# Module_Expansion_Mosfet.net
KiCad netlist of a schematic drawn in EAGLE
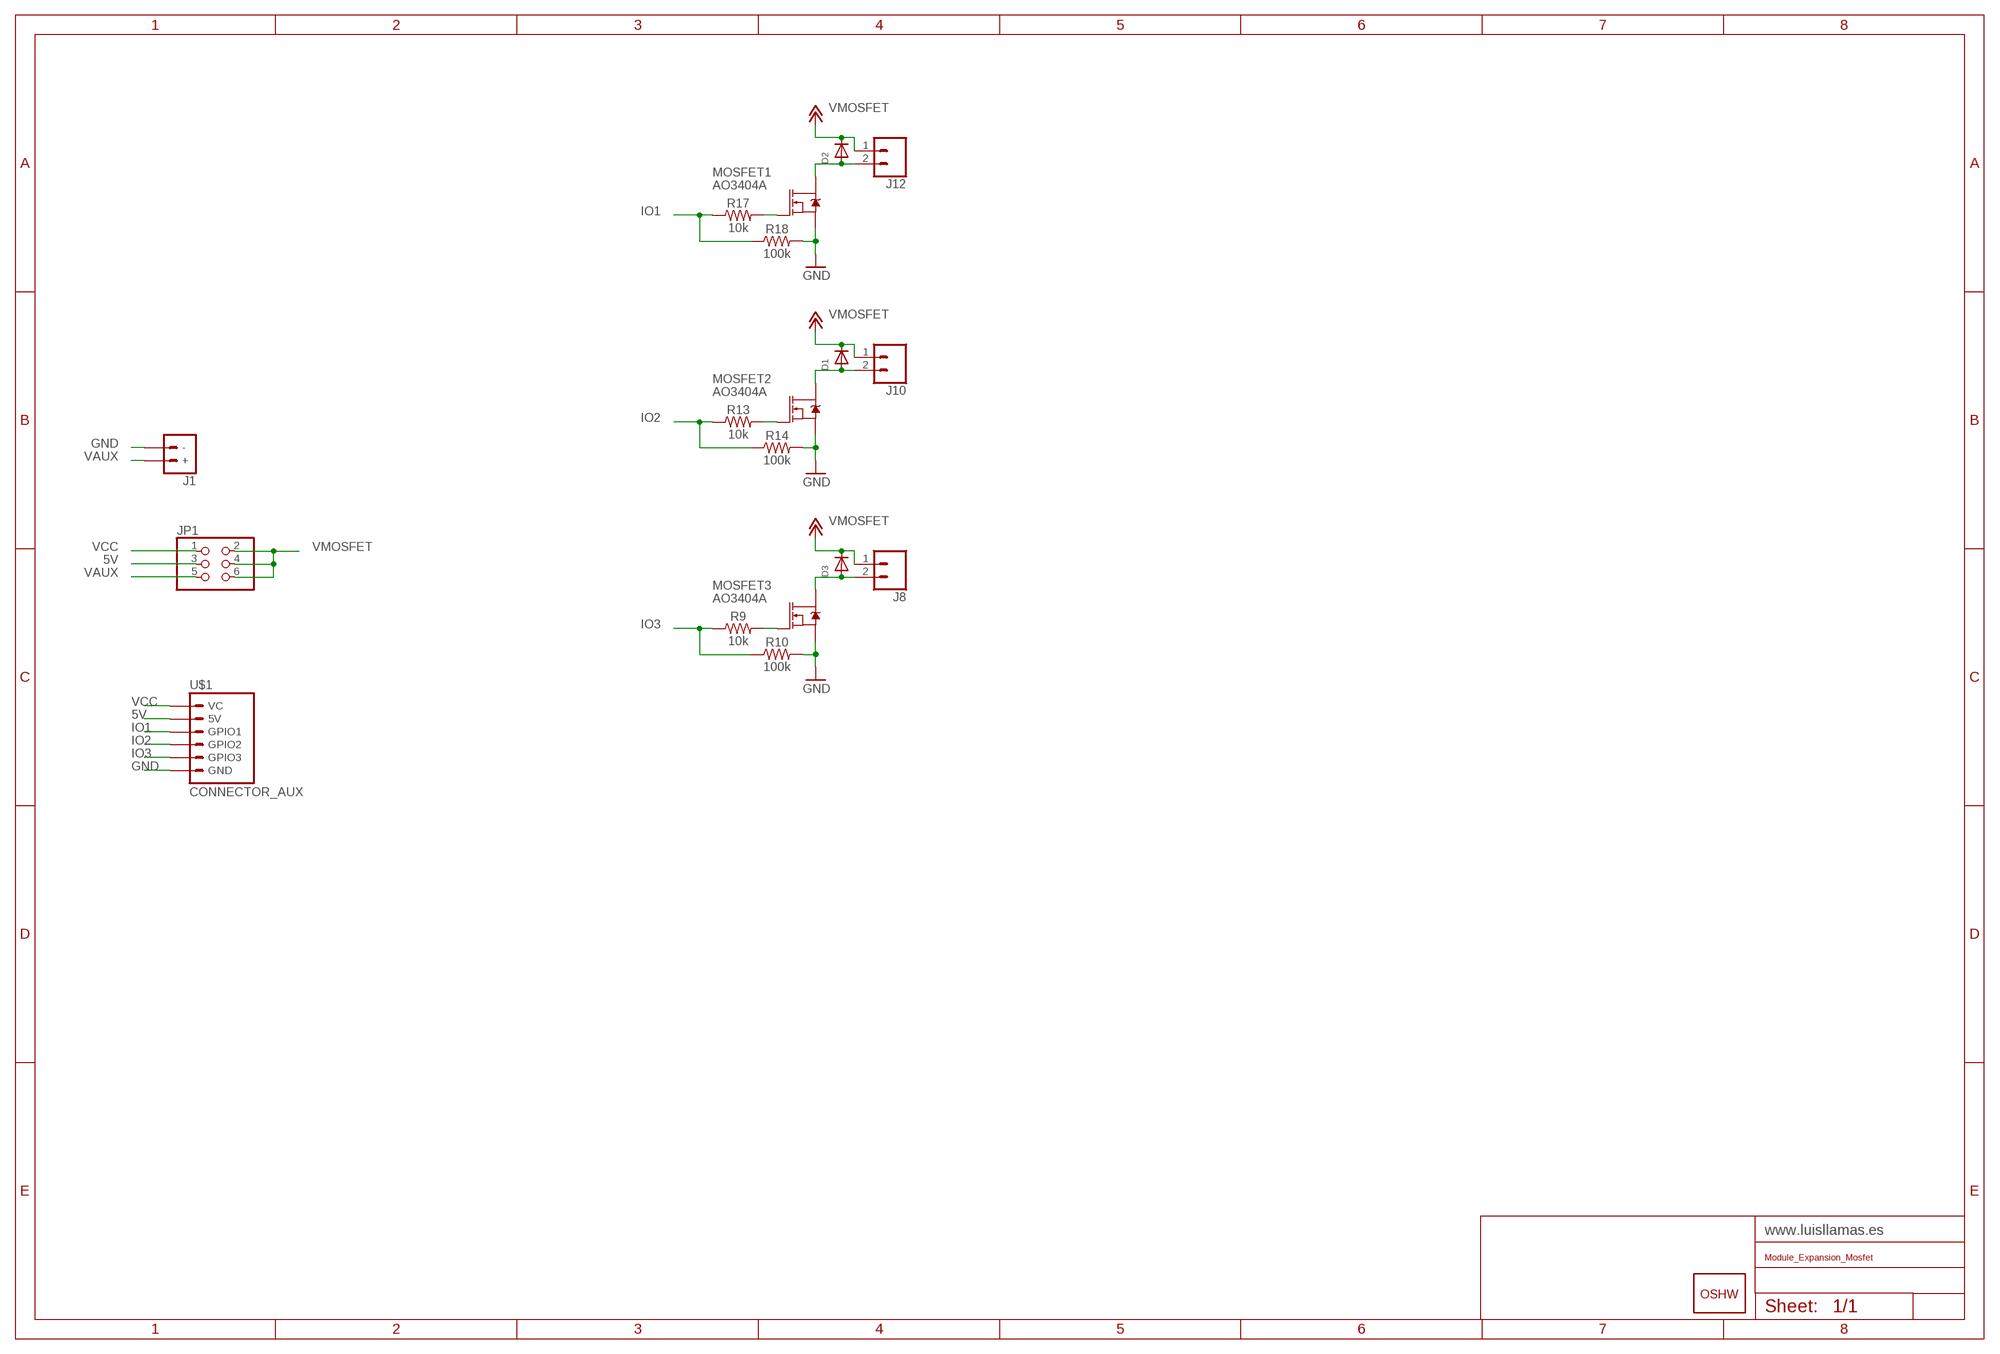
[diagram p0: schematic, sheet 1]

(export (version "E")
  (design (tool "Eeschema 10.0.6"))
  (components
    (comp (ref "D1")
      (value "DIODESOD-123")
      (footprint "eagle-import:SOD-123")
      (libsource (lib "eagle-import") (part "DIODESOD-123"))
    )
    (comp (ref "D2")
      (value "DIODESOD-123")
      (footprint "eagle-import:SOD-123")
      (libsource (lib "eagle-import") (part "DIODESOD-123"))
    )
    (comp (ref "D3")
      (value "DIODESOD-123")
      (footprint "eagle-import:SOD-123")
      (libsource (lib "eagle-import") (part "DIODESOD-123"))
    )
    (comp (ref "GOLD_ORB_SM1")
      (value "OSHWLOGO_GOLD_ORB_MED")
      (footprint "eagle-import:OSHW1")
      (libsource (lib "eagle-import") (part "OSHWLOGO_GOLD_ORB_MED"))
    )
    (comp (ref "J1")
      (value "POWER-TERMINAL2.54MM_SCREWTERM")
      (footprint "eagle-import:1X02_2.54_SCREWTERM")
      (libsource (lib "eagle-import") (part "POWER-TERMINAL2.54MM_SCREWTERM"))
    )
    (comp (ref "J8")
      (value "CONN_02LOCK_LONGPADS")
      (footprint "eagle-import:1X02_LOCK_LONGPADS")
      (libsource (lib "eagle-import") (part "CONN_02LOCK_LONGPADS"))
    )
    (comp (ref "J10")
      (value "CONN_02LOCK_LONGPADS")
      (footprint "eagle-import:1X02_LOCK_LONGPADS")
      (libsource (lib "eagle-import") (part "CONN_02LOCK_LONGPADS"))
    )
    (comp (ref "J12")
      (value "CONN_02LOCK_LONGPADS")
      (footprint "eagle-import:1X02_LOCK_LONGPADS")
      (libsource (lib "eagle-import") (part "CONN_02LOCK_LONGPADS"))
    )
    (comp (ref "JP1")
      (value "JUMPER_3X2/OCT")
      (footprint "eagle-import:JUMPER_3X2")
      (libsource (lib "eagle-import") (part "JUMPER_3X2/OCT"))
    )
    (comp (ref "MOSFET1")
      (value "AO3404A")
      (footprint "eagle-import:SOT23-3")
      (libsource (lib "eagle-import") (part "MOSFET-NCH-AO3404A"))
    )
    (comp (ref "MOSFET2")
      (value "AO3404A")
      (footprint "eagle-import:SOT23-3")
      (libsource (lib "eagle-import") (part "MOSFET-NCH-AO3404A"))
    )
    (comp (ref "MOSFET3")
      (value "AO3404A")
      (footprint "eagle-import:SOT23-3")
      (libsource (lib "eagle-import") (part "MOSFET-NCH-AO3404A"))
    )
    (comp (ref "R9")
      (value "10k")
      (footprint "eagle-import:1206")
      (libsource (lib "eagle-import") (part "RESISTOR1206"))
    )
    (comp (ref "R10")
      (value "100k")
      (footprint "eagle-import:1206")
      (libsource (lib "eagle-import") (part "RESISTOR1206"))
    )
    (comp (ref "R13")
      (value "10k")
      (footprint "eagle-import:1206")
      (libsource (lib "eagle-import") (part "RESISTOR1206"))
    )
    (comp (ref "R14")
      (value "100k")
      (footprint "eagle-import:1206")
      (libsource (lib "eagle-import") (part "RESISTOR1206"))
    )
    (comp (ref "R17")
      (value "10k")
      (footprint "eagle-import:1206")
      (libsource (lib "eagle-import") (part "RESISTOR1206"))
    )
    (comp (ref "R18")
      (value "100k")
      (footprint "eagle-import:1206")
      (libsource (lib "eagle-import") (part "RESISTOR1206"))
    )
    (comp (ref "U$1")
      (value "CONNECTOR_AUX")
      (footprint "eagle-import:CONNECTOR_AUX")
      (libsource (lib "eagle-import") (part "CONNECTOR_AUX"))
    )
  )
  (nets
    (net (code "1") (name "+12V") (class "Default")
      (node (ref "D1") (pin "C") (pinfunction "C_C") (pintype "passive"))
      (node (ref "D2") (pin "C") (pinfunction "C_C") (pintype "passive"))
      (node (ref "D3") (pin "C") (pinfunction "C_C") (pintype "passive"))
      (node (ref "J10") (pin "1") (pinfunction "1_1") (pintype "passive"))
      (node (ref "J12") (pin "1") (pinfunction "1_1") (pintype "passive"))
      (node (ref "J8") (pin "1") (pinfunction "1_1") (pintype "passive"))
      (node (ref "JP1") (pin "2") (pinfunction "2_2") (pintype "passive"))
      (node (ref "JP1") (pin "4") (pinfunction "4_4") (pintype "passive"))
      (node (ref "JP1") (pin "6") (pinfunction "6_6") (pintype "passive"))
    )
    (net (code "2") (name "/5V") (class "Default")
      (node (ref "JP1") (pin "3") (pinfunction "3_3") (pintype "passive"))
      (node (ref "U$1") (pin "5V") (pinfunction "5V_5V") (pintype "passive"))
    )
    (net (code "3") (name "/IO1") (class "Default")
      (node (ref "R17") (pin "1") (pinfunction "1_1") (pintype "passive"))
      (node (ref "R18") (pin "1") (pinfunction "1_1") (pintype "passive"))
      (node (ref "U$1") (pin "GPIO1") (pinfunction "GPIO1_GPIO1") (pintype "passive"))
    )
    (net (code "4") (name "/IO2") (class "Default")
      (node (ref "R13") (pin "1") (pinfunction "1_1") (pintype "passive"))
      (node (ref "R14") (pin "1") (pinfunction "1_1") (pintype "passive"))
      (node (ref "U$1") (pin "GPIO2") (pinfunction "GPIO2_GPIO2") (pintype "passive"))
    )
    (net (code "5") (name "/IO3") (class "Default")
      (node (ref "R10") (pin "1") (pinfunction "1_1") (pintype "passive"))
      (node (ref "R9") (pin "1") (pinfunction "1_1") (pintype "passive"))
      (node (ref "U$1") (pin "GPIO3") (pinfunction "GPIO3_GPIO3") (pintype "passive"))
    )
    (net (code "6") (name "/VAUX") (class "Default")
      (node (ref "J1") (pin "+") (pinfunction "+_+") (pintype "passive"))
      (node (ref "JP1") (pin "5") (pinfunction "5_5") (pintype "passive"))
    )
    (net (code "7") (name "/VCC") (class "Default")
      (node (ref "JP1") (pin "1") (pinfunction "1_1") (pintype "passive"))
      (node (ref "U$1") (pin "VC") (pinfunction "VC_VC") (pintype "passive"))
    )
    (net (code "8") (name "GND") (class "Default")
      (node (ref "J1") (pin "-") (pinfunction "-_-") (pintype "passive"))
      (node (ref "MOSFET1") (pin "2") (pinfunction "S_2") (pintype "bidirectional"))
      (node (ref "MOSFET2") (pin "2") (pinfunction "S_2") (pintype "bidirectional"))
      (node (ref "MOSFET3") (pin "2") (pinfunction "S_2") (pintype "bidirectional"))
      (node (ref "R10") (pin "2") (pinfunction "2_2") (pintype "passive"))
      (node (ref "R14") (pin "2") (pinfunction "2_2") (pintype "passive"))
      (node (ref "R18") (pin "2") (pinfunction "2_2") (pintype "passive"))
      (node (ref "U$1") (pin "GND") (pinfunction "GND_GND") (pintype "passive"))
    )
    (net (code "9") (name "Net-(MOSFET1-D)") (class "Default")
      (node (ref "D2") (pin "A") (pinfunction "A_A") (pintype "passive"))
      (node (ref "J12") (pin "2") (pinfunction "2_2") (pintype "passive"))
      (node (ref "MOSFET1") (pin "3") (pinfunction "D_3") (pintype "bidirectional"))
    )
    (net (code "10") (name "Net-(MOSFET1-G)") (class "Default")
      (node (ref "MOSFET1") (pin "1") (pinfunction "G_1") (pintype "bidirectional"))
      (node (ref "R17") (pin "2") (pinfunction "2_2") (pintype "passive"))
    )
    (net (code "11") (name "Net-(MOSFET2-D)") (class "Default")
      (node (ref "D1") (pin "A") (pinfunction "A_A") (pintype "passive"))
      (node (ref "J10") (pin "2") (pinfunction "2_2") (pintype "passive"))
      (node (ref "MOSFET2") (pin "3") (pinfunction "D_3") (pintype "bidirectional"))
    )
    (net (code "12") (name "Net-(MOSFET2-G)") (class "Default")
      (node (ref "MOSFET2") (pin "1") (pinfunction "G_1") (pintype "bidirectional"))
      (node (ref "R13") (pin "2") (pinfunction "2_2") (pintype "passive"))
    )
    (net (code "13") (name "Net-(MOSFET3-D)") (class "Default")
      (node (ref "D3") (pin "A") (pinfunction "A_A") (pintype "passive"))
      (node (ref "J8") (pin "2") (pinfunction "2_2") (pintype "passive"))
      (node (ref "MOSFET3") (pin "3") (pinfunction "D_3") (pintype "bidirectional"))
    )
    (net (code "14") (name "Net-(MOSFET3-G)") (class "Default")
      (node (ref "MOSFET3") (pin "1") (pinfunction "G_1") (pintype "bidirectional"))
      (node (ref "R9") (pin "2") (pinfunction "2_2") (pintype "passive"))
    )
  )
)
